# main.net
KiCad netlist of a schematic drawn in EAGLE
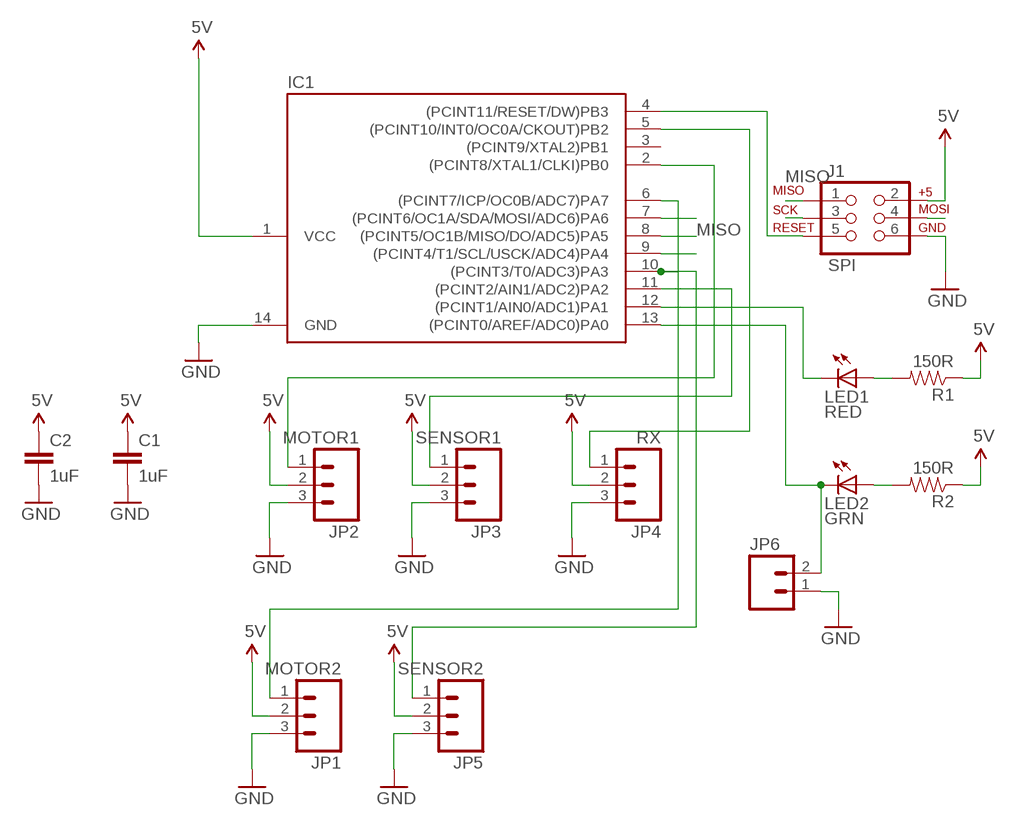
[diagram p0: schematic, sheet 1]

(export (version "E")
  (design (tool "Eeschema 10.0.6"))
  (components
    (comp (ref "C1")
      (value "1uF")
      (footprint "eagle-import:0805")
      (libsource (lib "eagle-import") (part "CAP0805"))
    )
    (comp (ref "C2")
      (value "1uF")
      (footprint "eagle-import:0805")
      (libsource (lib "eagle-import") (part "CAP0805"))
    )
    (comp (ref "IC1")
      (value "ATTINY24/44/84-SSU")
      (footprint "eagle-import:SOIC14")
      (libsource (lib "eagle-import") (part "ATTINY24/44/84-SSU"))
    )
    (comp (ref "J1")
      (value "SPI")
      (footprint "eagle-import:2X3_LOCK")
      (libsource (lib "eagle-import") (part "AVR_SPI_PRG_62X3_LOCK"))
    )
    (comp (ref "JP1")
      (value "MOTOR2")
      (footprint "eagle-import:1X03_LOCK")
      (libsource (lib "eagle-import") (part "M03LOCK"))
    )
    (comp (ref "JP2")
      (value "MOTOR1")
      (footprint "eagle-import:1X03_LOCK")
      (libsource (lib "eagle-import") (part "M03LOCK"))
    )
    (comp (ref "JP3")
      (value "SENSOR1")
      (footprint "eagle-import:1X03_LOCK")
      (libsource (lib "eagle-import") (part "M03LOCK"))
    )
    (comp (ref "JP4")
      (value "RX")
      (footprint "eagle-import:1X03_LOCK")
      (libsource (lib "eagle-import") (part "M03LOCK"))
    )
    (comp (ref "JP5")
      (value "SENSOR2")
      (footprint "eagle-import:1X03_LOCK")
      (libsource (lib "eagle-import") (part "M03LOCK"))
    )
    (comp (ref "JP6")
      (value "M02LOCK")
      (footprint "eagle-import:1X02_LOCK")
      (libsource (lib "eagle-import") (part "M02LOCK"))
    )
    (comp (ref "LED1")
      (value "RED")
      (footprint "eagle-import:LED3MM")
      (libsource (lib "eagle-import") (part "LED3MM"))
    )
    (comp (ref "LED2")
      (value "GRN")
      (footprint "eagle-import:LED3MM")
      (libsource (lib "eagle-import") (part "LED3MM"))
    )
    (comp (ref "R1")
      (value "150R")
      (footprint "eagle-import:0805")
      (libsource (lib "eagle-import") (part "RESISTOR0805-RES"))
    )
    (comp (ref "R2")
      (value "150R")
      (footprint "eagle-import:0805")
      (libsource (lib "eagle-import") (part "RESISTOR0805-RES"))
    )
  )
  (nets
    (net (code "1") (name "/MISO") (class "Default")
      (node (ref "IC1") (pin "8") (pinfunction "(PCINT5/OC1B/MISO/DO/ADC5)PA5_8") (pintype "bidirectional"))
      (node (ref "J1") (pin "1") (pinfunction "1_1") (pintype "passive"))
    )
    (net (code "2") (name "/MOSI") (class "Default")
      (node (ref "IC1") (pin "7") (pinfunction "(PCINT6/OC1A/SDA/MOSI/ADC6)PA6_7") (pintype "bidirectional"))
      (node (ref "J1") (pin "4") (pinfunction "4_4") (pintype "passive"))
    )
    (net (code "3") (name "/SCK") (class "Default")
      (node (ref "IC1") (pin "9") (pinfunction "(PCINT4/T1/SCL/USCK/ADC4)PA4_9") (pintype "bidirectional"))
      (node (ref "J1") (pin "3") (pinfunction "3_3") (pintype "passive"))
    )
    (net (code "4") (name "5V") (class "Default")
      (node (ref "C1") (pin "1") (pinfunction "1_1") (pintype "passive"))
      (node (ref "C2") (pin "1") (pinfunction "1_1") (pintype "passive"))
      (node (ref "IC1") (pin "1") (pinfunction "VCC_1") (pintype "power_in"))
      (node (ref "J1") (pin "2") (pinfunction "2_2") (pintype "passive"))
      (node (ref "JP1") (pin "2") (pinfunction "2_2") (pintype "passive"))
      (node (ref "JP2") (pin "2") (pinfunction "2_2") (pintype "passive"))
      (node (ref "JP3") (pin "2") (pinfunction "2_2") (pintype "passive"))
      (node (ref "JP4") (pin "2") (pinfunction "2_2") (pintype "passive"))
      (node (ref "JP5") (pin "2") (pinfunction "2_2") (pintype "passive"))
      (node (ref "R1") (pin "1") (pinfunction "1_1") (pintype "passive"))
      (node (ref "R2") (pin "1") (pinfunction "1_1") (pintype "passive"))
    )
    (net (code "5") (name "GND") (class "Default")
      (node (ref "C1") (pin "2") (pinfunction "2_2") (pintype "passive"))
      (node (ref "C2") (pin "2") (pinfunction "2_2") (pintype "passive"))
      (node (ref "IC1") (pin "14") (pinfunction "GND_14") (pintype "power_in"))
      (node (ref "J1") (pin "6") (pinfunction "6_6") (pintype "passive"))
      (node (ref "JP1") (pin "3") (pinfunction "3_3") (pintype "passive"))
      (node (ref "JP2") (pin "3") (pinfunction "3_3") (pintype "passive"))
      (node (ref "JP3") (pin "3") (pinfunction "3_3") (pintype "passive"))
      (node (ref "JP4") (pin "3") (pinfunction "3_3") (pintype "passive"))
      (node (ref "JP5") (pin "3") (pinfunction "3_3") (pintype "passive"))
      (node (ref "JP6") (pin "1") (pinfunction "1_1") (pintype "passive"))
    )
    (net (code "6") (name "Net-(IC1-(PCINT0{slash}AREF{slash}ADC0)PA0)") (class "Default")
      (node (ref "IC1") (pin "13") (pinfunction "(PCINT0/AREF/ADC0)PA0_13") (pintype "bidirectional"))
      (node (ref "JP6") (pin "2") (pinfunction "2_2") (pintype "passive"))
      (node (ref "LED2") (pin "K") (pinfunction "C_K") (pintype "passive"))
    )
    (net (code "7") (name "Net-(IC1-(PCINT1{slash}AIN0{slash}ADC1)PA1)") (class "Default")
      (node (ref "IC1") (pin "12") (pinfunction "(PCINT1/AIN0/ADC1)PA1_12") (pintype "bidirectional"))
      (node (ref "LED1") (pin "K") (pinfunction "C_K") (pintype "passive"))
    )
    (net (code "8") (name "Net-(IC1-(PCINT2{slash}AIN1{slash}ADC2)PA2)") (class "Default")
      (node (ref "IC1") (pin "11") (pinfunction "(PCINT2/AIN1/ADC2)PA2_11") (pintype "bidirectional"))
      (node (ref "JP3") (pin "1") (pinfunction "1_1") (pintype "passive"))
    )
    (net (code "9") (name "Net-(IC1-(PCINT3{slash}T0{slash}ADC3)PA3)") (class "Default")
      (node (ref "IC1") (pin "10") (pinfunction "(PCINT3/T0/ADC3)PA3_10") (pintype "bidirectional"))
      (node (ref "JP5") (pin "1") (pinfunction "1_1") (pintype "passive"))
    )
    (net (code "10") (name "Net-(IC1-(PCINT7{slash}ICP{slash}OC0B{slash}ADC7)PA7)") (class "Default")
      (node (ref "IC1") (pin "6") (pinfunction "(PCINT7/ICP/OC0B/ADC7)PA7_6") (pintype "bidirectional"))
      (node (ref "JP1") (pin "1") (pinfunction "1_1") (pintype "passive"))
    )
    (net (code "11") (name "Net-(IC1-(PCINT8{slash}XTAL1{slash}CLKI)PB0)") (class "Default")
      (node (ref "IC1") (pin "2") (pinfunction "(PCINT8/XTAL1/CLKI)PB0_2") (pintype "bidirectional"))
      (node (ref "JP2") (pin "1") (pinfunction "1_1") (pintype "passive"))
    )
    (net (code "12") (name "Net-(IC1-(PCINT10{slash}INT0{slash}OC0A{slash}CKOUT)PB2)") (class "Default")
      (node (ref "IC1") (pin "5") (pinfunction "(PCINT10/INT0/OC0A/CKOUT)PB2_5") (pintype "bidirectional"))
      (node (ref "JP4") (pin "1") (pinfunction "1_1") (pintype "passive"))
    )
    (net (code "13") (name "Net-(IC1-(PCINT11{slash}RESET{slash}DW)PB3)") (class "Default")
      (node (ref "IC1") (pin "4") (pinfunction "(PCINT11/RESET/DW)PB3_4") (pintype "bidirectional"))
      (node (ref "J1") (pin "5") (pinfunction "5_5") (pintype "passive"))
    )
    (net (code "14") (name "Net-(LED1-PadA)") (class "Default")
      (node (ref "LED1") (pin "A") (pinfunction "A_A") (pintype "passive"))
      (node (ref "R1") (pin "2") (pinfunction "2_2") (pintype "passive"))
    )
    (net (code "15") (name "Net-(LED2-PadA)") (class "Default")
      (node (ref "LED2") (pin "A") (pinfunction "A_A") (pintype "passive"))
      (node (ref "R2") (pin "2") (pinfunction "2_2") (pintype "passive"))
    )
    (net (code "16") (name "unconnected-(IC1-(PCINT9{slash}XTAL2)PB1-Pad3)") (class "Default")
      (node (ref "IC1") (pin "3") (pinfunction "(PCINT9/XTAL2)PB1_3") (pintype "bidirectional"))
    )
  )
)
